# convert_module.net
KiCad netlist of a schematic drawn in EAGLE
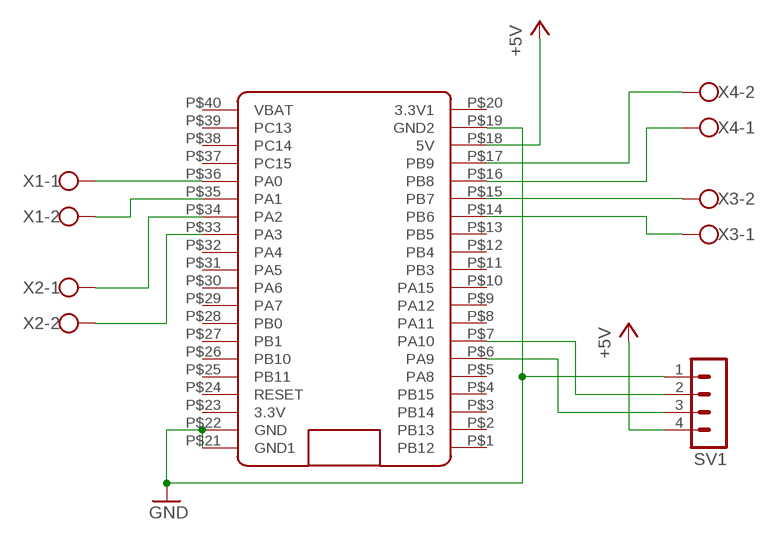
[diagram p0: schematic, sheet 1]
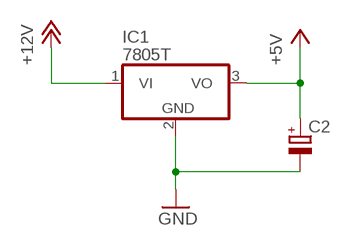
[diagram p1: schematic, sheet 2]
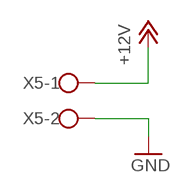
[diagram p2: schematic, sheet 3]

(export (version "E")
  (design (tool "Eeschema 10.0.6"))
  (components
    (comp (ref "C2")
      (value "CPOL-EUE2.5-5")
      (footprint "eagle-import:E2,5-5")
      (libsource (lib "eagle-import") (part "CPOL-EUE2.5-5"))
    )
    (comp (ref "IC1")
      (value "7805T")
      (footprint "eagle-import:TO220H")
      (libsource (lib "eagle-import") (part "78T05"))
    )
    (comp (ref "X5")
      (value "W237-102")
      (footprint "eagle-import:W237-102")
      (fields (field (name "MPN") "237-102"))
      (libsource (lib "eagle-import") (part "W237-102"))
    )
    (comp (ref "SV1")
      (value "MA04-1")
      (footprint "eagle-import:MA04-1")
      (libsource (lib "eagle-import") (part "MA04-1"))
    )
    (comp (ref "U$1")
      (value "BLUE_PILL")
      (footprint "eagle-import:BLUE_PILL")
      (libsource (lib "eagle-import") (part "BLUE_PILL"))
    )
    (comp (ref "X1")
      (value "W237-102")
      (footprint "eagle-import:W237-102")
      (fields (field (name "MPN") "237-102"))
      (libsource (lib "eagle-import") (part "W237-102"))
    )
    (comp (ref "X2")
      (value "W237-102")
      (footprint "eagle-import:W237-102")
      (fields (field (name "MPN") "237-102"))
      (libsource (lib "eagle-import") (part "W237-102"))
    )
    (comp (ref "X3")
      (value "W237-102")
      (footprint "eagle-import:W237-102")
      (fields (field (name "MPN") "237-102"))
      (libsource (lib "eagle-import") (part "W237-102"))
    )
    (comp (ref "X4")
      (value "W237-102")
      (footprint "eagle-import:W237-102")
      (fields (field (name "MPN") "237-102"))
      (libsource (lib "eagle-import") (part "W237-102"))
    )
  )
  (nets
    (net (code "1") (name "+5V") (class "Default")
      (node (ref "C2") (pin "+") (pinfunction "+_+") (pintype "passive"))
      (node (ref "IC1") (pin "3") (pinfunction "VO_3") (pintype "passive"))
      (node (ref "SV1") (pin "4") (pinfunction "4_4") (pintype "passive"))
      (node (ref "U$1") (pin "P$18") (pinfunction "5V_P$18") (pintype "bidirectional"))
    )
    (net (code "2") (name "+12V") (class "Default")
      (node (ref "IC1") (pin "1") (pinfunction "VI_1") (pintype "input"))
      (node (ref "X5") (pin "1") (pinfunction "KL_1") (pintype "passive"))
    )
    (net (code "3") (name "GND") (class "Default")
      (node (ref "C2") (pin "-") (pinfunction "-_-") (pintype "passive"))
      (node (ref "IC1") (pin "2") (pinfunction "GND_2") (pintype "passive"))
      (node (ref "SV1") (pin "1") (pinfunction "1_1") (pintype "passive"))
      (node (ref "U$1") (pin "P$19") (pinfunction "GND2_P$19") (pintype "bidirectional"))
      (node (ref "U$1") (pin "P$21") (pinfunction "GND1_P$21") (pintype "power_in"))
      (node (ref "U$1") (pin "P$22") (pinfunction "GND_P$22") (pintype "bidirectional"))
      (node (ref "X5") (pin "2") (pinfunction "KL_2") (pintype "passive"))
    )
    (net (code "4") (name "Net-(U$1-PA0)") (class "Default")
      (node (ref "U$1") (pin "P$36") (pinfunction "PA0_P$36") (pintype "bidirectional"))
      (node (ref "X1") (pin "1") (pinfunction "KL_1") (pintype "passive"))
    )
    (net (code "5") (name "Net-(U$1-PA1)") (class "Default")
      (node (ref "U$1") (pin "P$35") (pinfunction "PA1_P$35") (pintype "bidirectional"))
      (node (ref "X1") (pin "2") (pinfunction "KL_2") (pintype "passive"))
    )
    (net (code "6") (name "Net-(U$1-PA2)") (class "Default")
      (node (ref "U$1") (pin "P$34") (pinfunction "PA2_P$34") (pintype "bidirectional"))
      (node (ref "X2") (pin "1") (pinfunction "KL_1") (pintype "passive"))
    )
    (net (code "7") (name "Net-(U$1-PA3)") (class "Default")
      (node (ref "U$1") (pin "P$33") (pinfunction "PA3_P$33") (pintype "bidirectional"))
      (node (ref "X2") (pin "2") (pinfunction "KL_2") (pintype "passive"))
    )
    (net (code "8") (name "Net-(U$1-PA9)") (class "Default")
      (node (ref "SV1") (pin "3") (pinfunction "3_3") (pintype "passive"))
      (node (ref "U$1") (pin "P$6") (pinfunction "PA9_P$6") (pintype "bidirectional"))
    )
    (net (code "9") (name "Net-(U$1-PA10)") (class "Default")
      (node (ref "SV1") (pin "2") (pinfunction "2_2") (pintype "passive"))
      (node (ref "U$1") (pin "P$7") (pinfunction "PA10_P$7") (pintype "bidirectional"))
    )
    (net (code "10") (name "Net-(U$1-PB6)") (class "Default")
      (node (ref "U$1") (pin "P$14") (pinfunction "PB6_P$14") (pintype "bidirectional"))
      (node (ref "X3") (pin "1") (pinfunction "KL_1") (pintype "passive"))
    )
    (net (code "11") (name "Net-(U$1-PB7)") (class "Default")
      (node (ref "U$1") (pin "P$15") (pinfunction "PB7_P$15") (pintype "bidirectional"))
      (node (ref "X3") (pin "2") (pinfunction "KL_2") (pintype "passive"))
    )
    (net (code "12") (name "Net-(U$1-PB8)") (class "Default")
      (node (ref "U$1") (pin "P$16") (pinfunction "PB8_P$16") (pintype "bidirectional"))
      (node (ref "X4") (pin "1") (pinfunction "KL_1") (pintype "passive"))
    )
    (net (code "13") (name "Net-(U$1-PB9)") (class "Default")
      (node (ref "U$1") (pin "P$17") (pinfunction "PB9_P$17") (pintype "bidirectional"))
      (node (ref "X4") (pin "2") (pinfunction "KL_2") (pintype "passive"))
    )
    (net (code "14") (name "unconnected-(U$1-3.3V-PadP$23)") (class "Default")
      (node (ref "U$1") (pin "P$23") (pinfunction "3.3V_P$23") (pintype "bidirectional"))
    )
    (net (code "15") (name "unconnected-(U$1-3.3V1-PadP$20)") (class "Default")
      (node (ref "U$1") (pin "P$20") (pinfunction "3.3V1_P$20") (pintype "bidirectional"))
    )
    (net (code "16") (name "unconnected-(U$1-PA4-PadP$32)") (class "Default")
      (node (ref "U$1") (pin "P$32") (pinfunction "PA4_P$32") (pintype "bidirectional"))
    )
    (net (code "17") (name "unconnected-(U$1-PA5-PadP$31)") (class "Default")
      (node (ref "U$1") (pin "P$31") (pinfunction "PA5_P$31") (pintype "bidirectional"))
    )
    (net (code "18") (name "unconnected-(U$1-PA6-PadP$30)") (class "Default")
      (node (ref "U$1") (pin "P$30") (pinfunction "PA6_P$30") (pintype "bidirectional"))
    )
    (net (code "19") (name "unconnected-(U$1-PA7-PadP$29)") (class "Default")
      (node (ref "U$1") (pin "P$29") (pinfunction "PA7_P$29") (pintype "bidirectional"))
    )
    (net (code "20") (name "unconnected-(U$1-PA8-PadP$5)") (class "Default")
      (node (ref "U$1") (pin "P$5") (pinfunction "PA8_P$5") (pintype "bidirectional"))
    )
    (net (code "21") (name "unconnected-(U$1-PA11-PadP$8)") (class "Default")
      (node (ref "U$1") (pin "P$8") (pinfunction "PA11_P$8") (pintype "bidirectional"))
    )
    (net (code "22") (name "unconnected-(U$1-PA12-PadP$9)") (class "Default")
      (node (ref "U$1") (pin "P$9") (pinfunction "PA12_P$9") (pintype "bidirectional"))
    )
    (net (code "23") (name "unconnected-(U$1-PA15-PadP$10)") (class "Default")
      (node (ref "U$1") (pin "P$10") (pinfunction "PA15_P$10") (pintype "bidirectional"))
    )
    (net (code "24") (name "unconnected-(U$1-PB0-PadP$28)") (class "Default")
      (node (ref "U$1") (pin "P$28") (pinfunction "PB0_P$28") (pintype "bidirectional"))
    )
    (net (code "25") (name "unconnected-(U$1-PB1-PadP$27)") (class "Default")
      (node (ref "U$1") (pin "P$27") (pinfunction "PB1_P$27") (pintype "bidirectional"))
    )
    (net (code "26") (name "unconnected-(U$1-PB3-PadP$11)") (class "Default")
      (node (ref "U$1") (pin "P$11") (pinfunction "PB3_P$11") (pintype "bidirectional"))
    )
    (net (code "27") (name "unconnected-(U$1-PB4-PadP$12)") (class "Default")
      (node (ref "U$1") (pin "P$12") (pinfunction "PB4_P$12") (pintype "bidirectional"))
    )
    (net (code "28") (name "unconnected-(U$1-PB5-PadP$13)") (class "Default")
      (node (ref "U$1") (pin "P$13") (pinfunction "PB5_P$13") (pintype "bidirectional"))
    )
    (net (code "29") (name "unconnected-(U$1-PB10-PadP$26)") (class "Default")
      (node (ref "U$1") (pin "P$26") (pinfunction "PB10_P$26") (pintype "bidirectional"))
    )
    (net (code "30") (name "unconnected-(U$1-PB11-PadP$25)") (class "Default")
      (node (ref "U$1") (pin "P$25") (pinfunction "PB11_P$25") (pintype "bidirectional"))
    )
    (net (code "31") (name "unconnected-(U$1-PB12-PadP$1)") (class "Default")
      (node (ref "U$1") (pin "P$1") (pinfunction "PB12_P$1") (pintype "bidirectional"))
    )
    (net (code "32") (name "unconnected-(U$1-PB13-PadP$2)") (class "Default")
      (node (ref "U$1") (pin "P$2") (pinfunction "PB13_P$2") (pintype "bidirectional"))
    )
    (net (code "33") (name "unconnected-(U$1-PB14-PadP$3)") (class "Default")
      (node (ref "U$1") (pin "P$3") (pinfunction "PB14_P$3") (pintype "bidirectional"))
    )
    (net (code "34") (name "unconnected-(U$1-PB15-PadP$4)") (class "Default")
      (node (ref "U$1") (pin "P$4") (pinfunction "PB15_P$4") (pintype "bidirectional"))
    )
    (net (code "35") (name "unconnected-(U$1-PC13-PadP$39)") (class "Default")
      (node (ref "U$1") (pin "P$39") (pinfunction "PC13_P$39") (pintype "bidirectional"))
    )
    (net (code "36") (name "unconnected-(U$1-PC14-PadP$38)") (class "Default")
      (node (ref "U$1") (pin "P$38") (pinfunction "PC14_P$38") (pintype "bidirectional"))
    )
    (net (code "37") (name "unconnected-(U$1-PC15-PadP$37)") (class "Default")
      (node (ref "U$1") (pin "P$37") (pinfunction "PC15_P$37") (pintype "bidirectional"))
    )
    (net (code "38") (name "unconnected-(U$1-RESET-PadP$24)") (class "Default")
      (node (ref "U$1") (pin "P$24") (pinfunction "RESET_P$24") (pintype "bidirectional"))
    )
    (net (code "39") (name "unconnected-(U$1-VBAT-PadP$40)") (class "Default")
      (node (ref "U$1") (pin "P$40") (pinfunction "VBAT_P$40") (pintype "bidirectional"))
    )
  )
)
